# 10_-_IO.net
KiCad netlist of a schematic drawn in Altium Designer
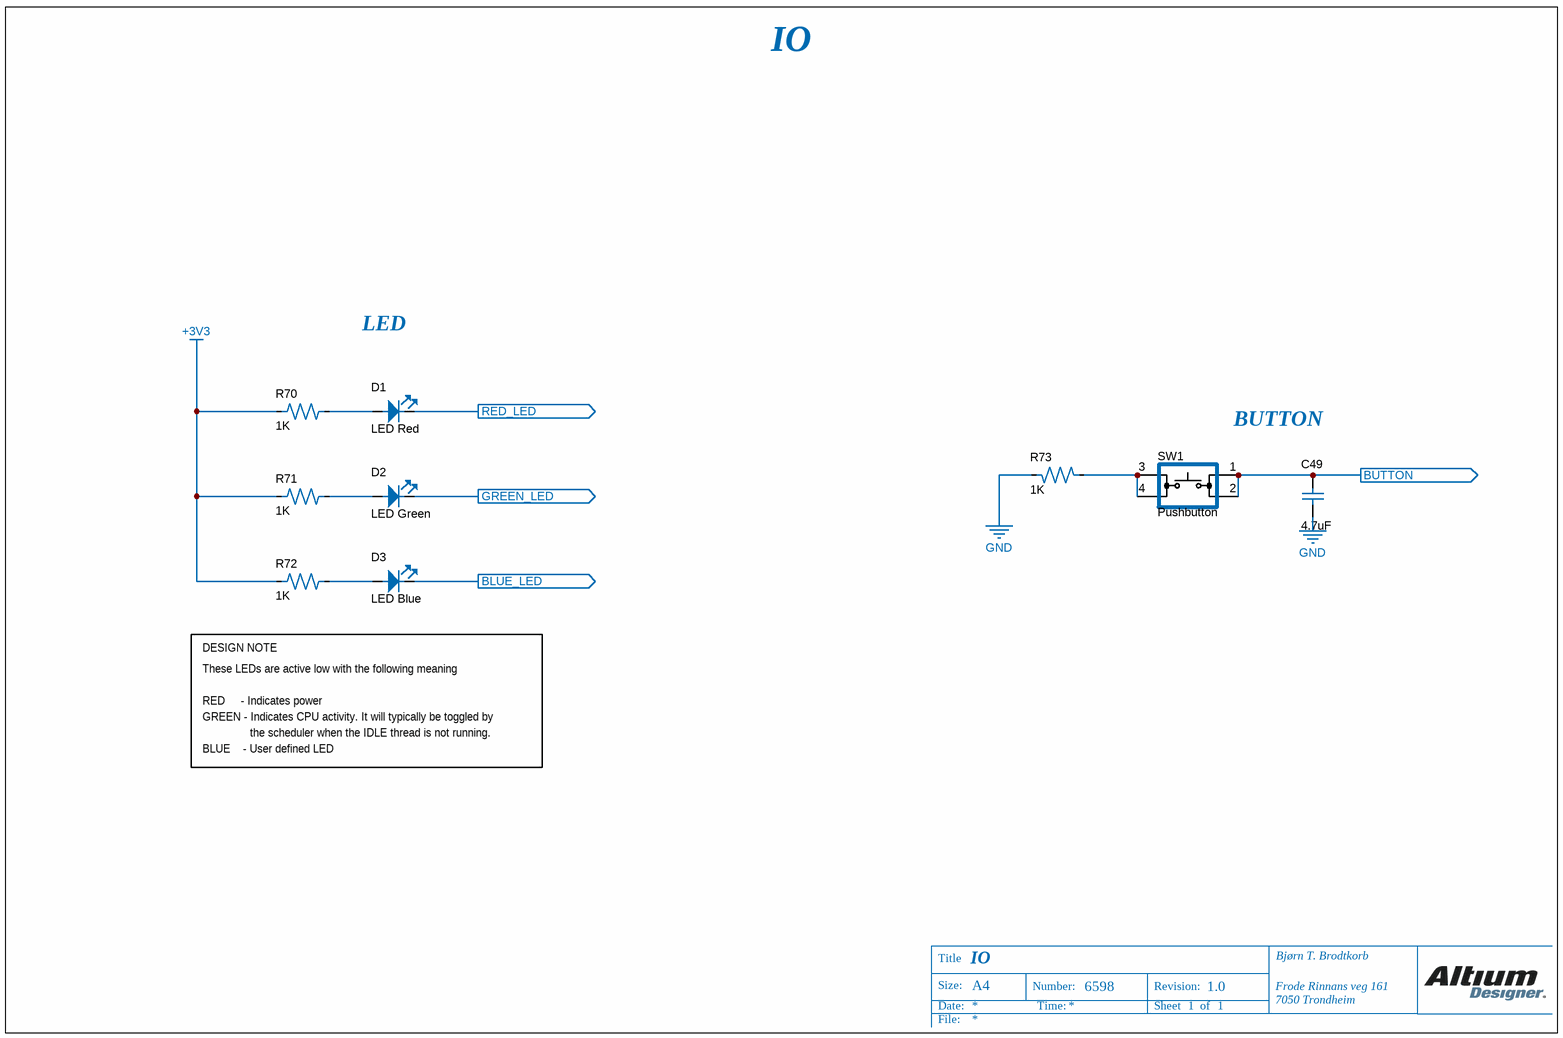
[diagram p0: [10] - IO.SchDoc]

(export (version "E")
  (design (tool "Eeschema 10.0.6"))
  (components
    (comp (ref "C49")
      (value "4.7uF")
      (footprint "C0603")
      (description "C0603")
      (fields (field (name "Comment") "02016D104KAT2A"))
      (libsource (lib "Passive components") (part "02016D104KAT2A"))
    )
    (comp (ref "D1")
      (value "LED Red")
      (footprint "L0603 RED")
      (description "LED 0603 Red")
      (libsource (lib "Diodes") (part "HSMG-C190"))
    )
    (comp (ref "D2")
      (value "LED Green")
      (footprint "L0603 GREEN")
      (description "LED 0603 Green")
      (libsource (lib "Diodes") (part "HSMG-C196"))
    )
    (comp (ref "D3")
      (value "LED Blue")
      (footprint "L0603 BLUE")
      (description "LED 0603 Blue")
      (libsource (lib "Diodes") (part "HSMG-C199"))
    )
    (comp (ref "R70")
      (value "1K")
      (footprint "R0402")
      (description "R0402")
      (fields (field (name "Comment") "CRCW04020000Z0ED"))
      (libsource (lib "Passive components") (part "CRCW04020000Z0ED"))
    )
    (comp (ref "R71")
      (value "1K")
      (footprint "R0402")
      (description "R0402")
      (fields (field (name "Comment") "CRCW04020000Z0ED"))
      (libsource (lib "Passive components") (part "CRCW04020000Z0ED"))
    )
    (comp (ref "R72")
      (value "1K")
      (footprint "R0402")
      (description "R0402")
      (fields (field (name "Comment") "CRCW04020000Z0ED"))
      (libsource (lib "Passive components") (part "CRCW04020000Z0ED"))
    )
    (comp (ref "R73")
      (value "1K")
      (footprint "R0603")
      (description "R0603")
      (fields (field (name "Comment") "CPF-A-0603B100KE1"))
      (libsource (lib "Passive components") (part "CPF-A-0603B100KE1"))
    )
    (comp (ref "SW1")
      (value "Pushbutton")
      (footprint "KSC222G LFS")
      (description "Pushbutton SMD")
      (libsource (lib "Sensors") (part "KSC222G LFS"))
    )
  )
  (nets
    (net (code "1") (name "+3V3") (class "Default")
      (node (ref "R70") (pin "1") (pinfunction "1_1") (pintype "passive"))
      (node (ref "R71") (pin "1") (pinfunction "1_1") (pintype "passive"))
      (node (ref "R72") (pin "1") (pinfunction "1_1") (pintype "passive"))
    )
    (net (code "2") (name "/BLUE_LED") (class "Default")
      (node (ref "D3") (pin "2") (pinfunction "2_2") (pintype "passive"))
    )
    (net (code "3") (name "/BUTTON") (class "Default")
      (node (ref "C49") (pin "2") (pinfunction "2_2") (pintype "passive"))
      (node (ref "SW1") (pin "1") (pinfunction "1_1") (pintype "passive"))
      (node (ref "SW1") (pin "2") (pinfunction "2_2") (pintype "passive"))
    )
    (net (code "4") (name "/GREEN_LED") (class "Default")
      (node (ref "D2") (pin "2") (pinfunction "2_2") (pintype "passive"))
    )
    (net (code "5") (name "/RED_LED") (class "Default")
      (node (ref "D1") (pin "2") (pinfunction "2_2") (pintype "passive"))
    )
    (net (code "6") (name "GND") (class "Default")
      (node (ref "C49") (pin "1") (pinfunction "1_1") (pintype "passive"))
      (node (ref "R73") (pin "2") (pinfunction "2_2") (pintype "passive"))
    )
    (net (code "7") (name "Net-(R70-3)") (class "Default")
      (node (ref "D1") (pin "1") (pinfunction "1_1") (pintype "passive"))
      (node (ref "R70") (pin "2") (pinfunction "3_2") (pintype "passive"))
    )
    (net (code "8") (name "Net-(R71-3)") (class "Default")
      (node (ref "D2") (pin "1") (pinfunction "1_1") (pintype "passive"))
      (node (ref "R71") (pin "2") (pinfunction "3_2") (pintype "passive"))
    )
    (net (code "9") (name "Net-(R72-3)") (class "Default")
      (node (ref "D3") (pin "1") (pinfunction "1_1") (pintype "passive"))
      (node (ref "R72") (pin "2") (pinfunction "3_2") (pintype "passive"))
    )
    (net (code "10") (name "Net-(R73-Pad1)") (class "Default")
      (node (ref "R73") (pin "1") (pinfunction "1_1") (pintype "passive"))
      (node (ref "SW1") (pin "3") (pinfunction "3_3") (pintype "passive"))
      (node (ref "SW1") (pin "4") (pinfunction "4_4") (pintype "passive"))
    )
  )
)
